# connector-schematic.net
KiCad netlist of a schematic drawn in Altium Designer
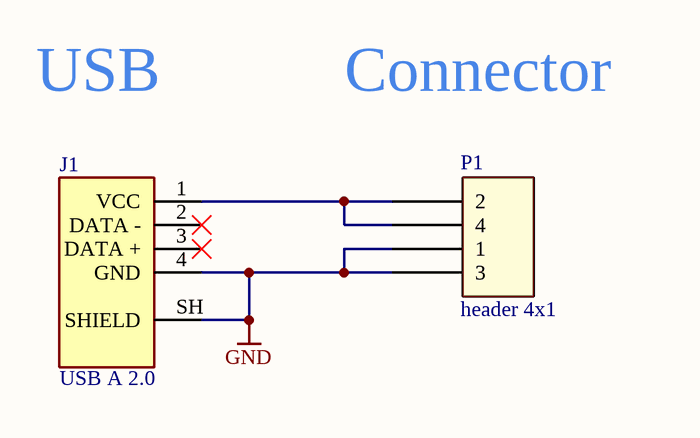
[diagram p0: connector-schematic.SchDoc]

(export (version "E")
  (design (tool "Eeschema 10.0.6"))
  (components
    (comp (ref "J1")
      (value "USB A 2.0")
      (footprint "0480372100")
      (description "Type A, USB 2.0, 1 A, Vertical, Through Hole, USB Receptacle")
      (fields (field (name "MP") "UJ2-AV-2-TH") (field (name "MF") "CUI Devices"))
      (libsource (lib "USBHUB") (part "USB A 2.0"))
    )
    (comp (ref "P1")
      (value "header 4x1")
      (footprint "4x1, 2.54mm, smd side")
      (libsource (lib "USBHUB") (part "header 4x1"))
    )
  )
  (nets
    (net (code "1") (name "GND") (class "Default")
      (node (ref "J1") (pin "4") (pinfunction "GND_4") (pintype "passive"))
      (node (ref "J1") (pin "SH") (pinfunction "SHIELD_SH") (pintype "passive"))
      (node (ref "P1") (pin "1") (pinfunction "1_1") (pintype "passive"))
      (node (ref "P1") (pin "3") (pinfunction "3_3") (pintype "passive"))
    )
    (net (code "2") (name "Net-(J1-VCC)") (class "Default")
      (node (ref "J1") (pin "1") (pinfunction "VCC_1") (pintype "passive"))
      (node (ref "P1") (pin "2") (pinfunction "2_2") (pintype "passive"))
      (node (ref "P1") (pin "4") (pinfunction "4_4") (pintype "passive"))
    )
    (net (code "3") (name "unconnected-(J1-DATA_+-Pad3)") (class "Default")
      (node (ref "J1") (pin "3") (pinfunction "DATA_+_3") (pintype "passive+no_connect"))
    )
    (net (code "4") (name "unconnected-(J1-DATA_--Pad2)") (class "Default")
      (node (ref "J1") (pin "2") (pinfunction "DATA_-_2") (pintype "passive+no_connect"))
    )
  )
)
